# touch_rev1.net
KiCad netlist of a schematic drawn in EAGLE
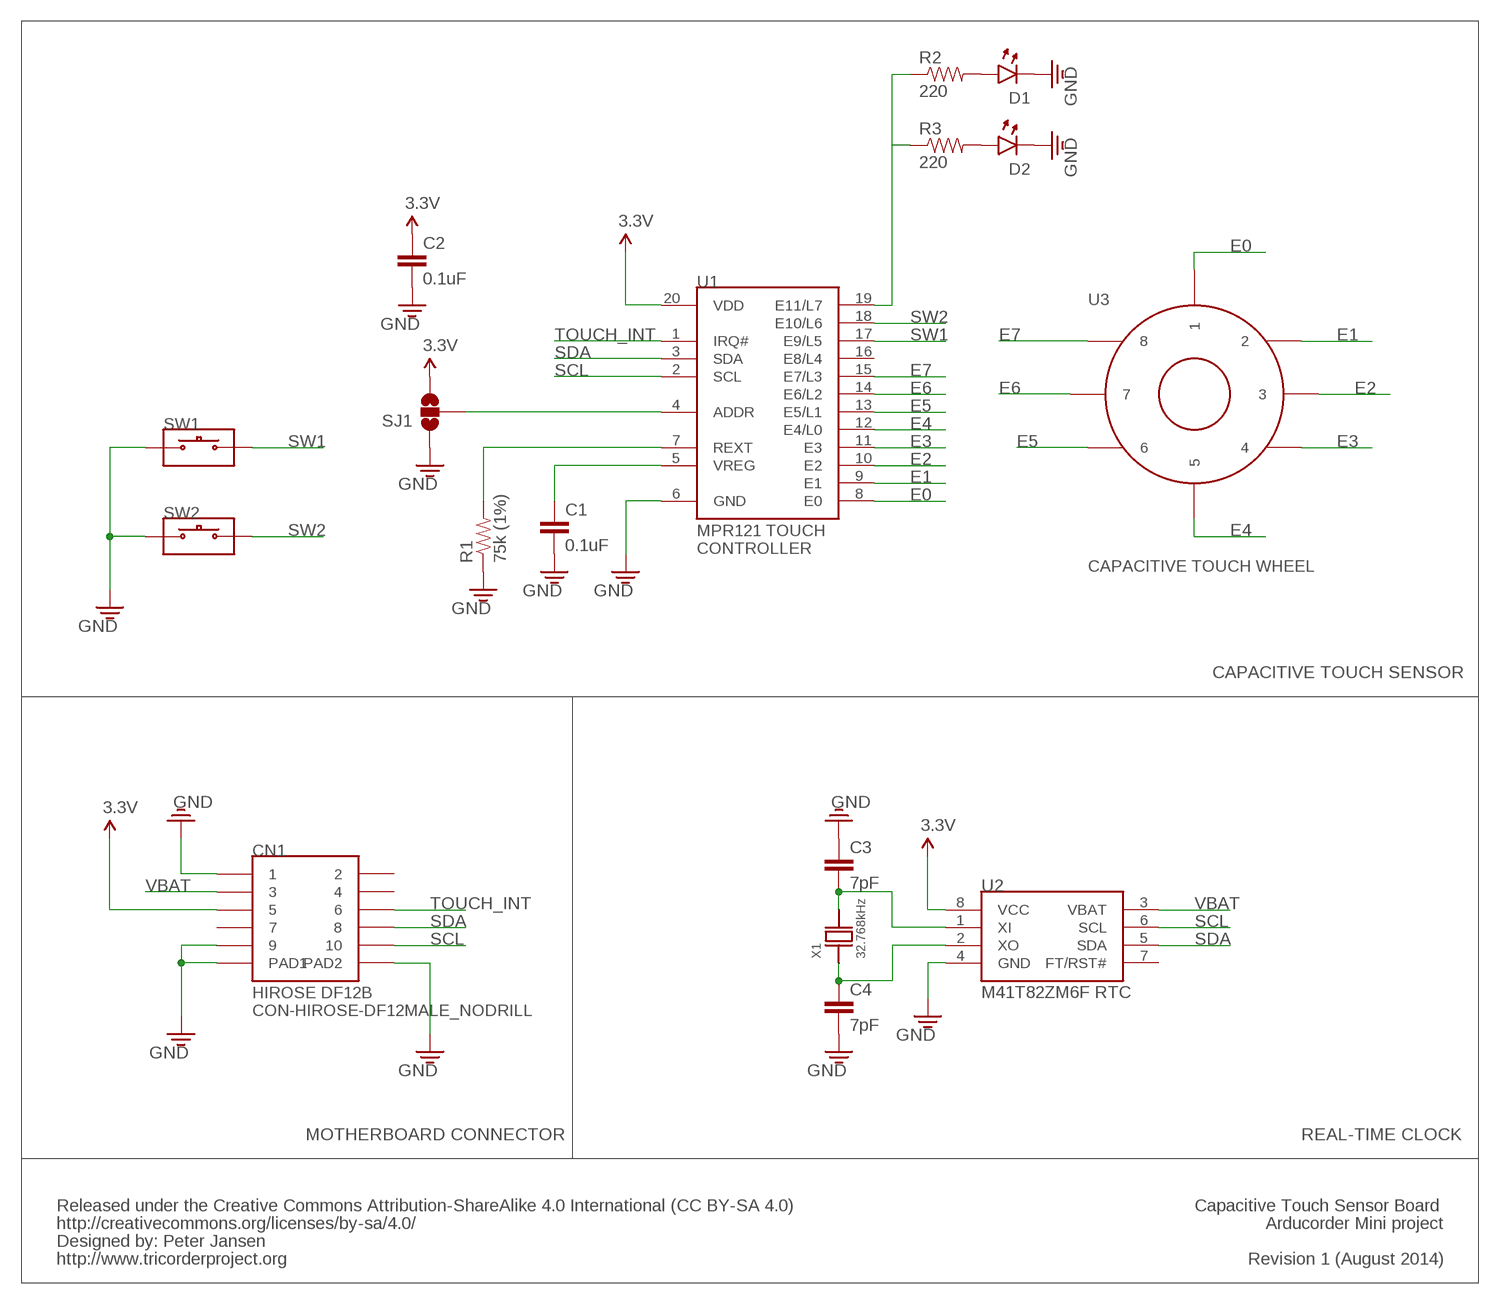
[diagram p0: schematic, sheet 1]

(export (version "E")
  (design (tool "Eeschema 10.0.6"))
  (components
    (comp (ref "C1")
      (value "0.1uF")
      (footprint "eagle-import:0603")
      (libsource (lib "eagle-import") (part "CAP0603"))
    )
    (comp (ref "C2")
      (value "0.1uF")
      (footprint "eagle-import:0603")
      (libsource (lib "eagle-import") (part "CAP0603"))
    )
    (comp (ref "C3")
      (value "7pF")
      (footprint "eagle-import:0603")
      (libsource (lib "eagle-import") (part "CAP0603"))
    )
    (comp (ref "C4")
      (value "7pF")
      (footprint "eagle-import:0603")
      (libsource (lib "eagle-import") (part "CAP0603"))
    )
    (comp (ref "CN1")
      (value "CON-HIROSE-DF12MALE_NODRILL")
      (footprint "eagle-import:DF12(3.0)-10DS-0.5V(86)")
      (libsource (lib "eagle-import") (part "CON-HIROSE-DF12MALE_NODRILL"))
    )
    (comp (ref "D1")
      (value "0605-LED")
      (footprint "eagle-import:0603-LED")
      (libsource (lib "eagle-import") (part "0605-LED"))
    )
    (comp (ref "D2")
      (value "0605-LED")
      (footprint "eagle-import:0603-LED")
      (libsource (lib "eagle-import") (part "0605-LED"))
    )
    (comp (ref "R1")
      (value "75k (1%)")
      (footprint "eagle-import:0603")
      (libsource (lib "eagle-import") (part "RESISTOR0603"))
    )
    (comp (ref "R2")
      (value "220")
      (footprint "eagle-import:0603")
      (libsource (lib "eagle-import") (part "RESISTOR0603"))
    )
    (comp (ref "R3")
      (value "220")
      (footprint "eagle-import:0603")
      (libsource (lib "eagle-import") (part "RESISTOR0603"))
    )
    (comp (ref "SJ1")
      (value "SOLDERJUMPER_2WAYPASTE1&2")
      (footprint "eagle-import:SJ_3_PASTE1&2")
      (libsource (lib "eagle-import") (part "SOLDERJUMPER_2WAYPASTE1&2"))
    )
    (comp (ref "SW1")
      (value "SWITCH")
      (footprint "eagle-import:KMT071")
      (libsource (lib "eagle-import") (part "SWITCH"))
    )
    (comp (ref "SW2")
      (value "SWITCH")
      (footprint "eagle-import:KMT071")
      (libsource (lib "eagle-import") (part "SWITCH"))
    )
    (comp (ref "U1")
      (value "MPR121-TOUCH-CONTROLLER")
      (footprint "eagle-import:QFN-3X3-20")
      (libsource (lib "eagle-import") (part "MPR121-TOUCH-CONTROLLER"))
    )
    (comp (ref "U2")
      (value "M41T82ZM6F")
      (footprint "eagle-import:8-SOIC")
      (libsource (lib "eagle-import") (part "M41T82ZM6F"))
    )
    (comp (ref "U3")
      (value "CAPACITIVE-WHEEL-8")
      (footprint "eagle-import:CAPACITIVE-WHEEL-8")
      (libsource (lib "eagle-import") (part "CAPACITIVE-WHEEL-8"))
    )
    (comp (ref "X1")
      (value "32.768kHz")
      (footprint "eagle-import:CRYSTAL-9HT10")
      (libsource (lib "eagle-import") (part "CRYSTAL"))
    )
  )
  (nets
    (net (code "1") (name "/E0") (class "Default")
      (node (ref "U1") (pin "8") (pinfunction "E0_8") (pintype "bidirectional"))
      (node (ref "U3") (pin "1") (pinfunction "1_1") (pintype "bidirectional"))
    )
    (net (code "2") (name "/E1") (class "Default")
      (node (ref "U1") (pin "9") (pinfunction "E1_9") (pintype "bidirectional"))
      (node (ref "U3") (pin "2") (pinfunction "2_2") (pintype "bidirectional"))
    )
    (net (code "3") (name "/E2") (class "Default")
      (node (ref "U1") (pin "10") (pinfunction "E2_10") (pintype "bidirectional"))
      (node (ref "U3") (pin "3") (pinfunction "3_3") (pintype "bidirectional"))
    )
    (net (code "4") (name "/E3") (class "Default")
      (node (ref "U1") (pin "11") (pinfunction "E3_11") (pintype "bidirectional"))
      (node (ref "U3") (pin "4") (pinfunction "4_4") (pintype "bidirectional"))
    )
    (net (code "5") (name "/E4") (class "Default")
      (node (ref "U1") (pin "12") (pinfunction "E4/L0_12") (pintype "bidirectional"))
      (node (ref "U3") (pin "5") (pinfunction "5_5") (pintype "bidirectional"))
    )
    (net (code "6") (name "/E5") (class "Default")
      (node (ref "U1") (pin "13") (pinfunction "E5/L1_13") (pintype "bidirectional"))
      (node (ref "U3") (pin "6") (pinfunction "6_6") (pintype "bidirectional"))
    )
    (net (code "7") (name "/E6") (class "Default")
      (node (ref "U1") (pin "14") (pinfunction "E6/L2_14") (pintype "bidirectional"))
      (node (ref "U3") (pin "7") (pinfunction "7_7") (pintype "bidirectional"))
    )
    (net (code "8") (name "/E7") (class "Default")
      (node (ref "U1") (pin "15") (pinfunction "E7/L3_15") (pintype "bidirectional"))
      (node (ref "U3") (pin "8") (pinfunction "8_8") (pintype "bidirectional"))
    )
    (net (code "9") (name "/SCL") (class "Default")
      (node (ref "CN1") (pin "10") (pinfunction "10_10") (pintype "bidirectional"))
      (node (ref "U1") (pin "2") (pinfunction "SCL_2") (pintype "bidirectional"))
      (node (ref "U2") (pin "6") (pinfunction "SCL_6") (pintype "bidirectional"))
    )
    (net (code "10") (name "/SDA") (class "Default")
      (node (ref "CN1") (pin "8") (pinfunction "8_8") (pintype "bidirectional"))
      (node (ref "U1") (pin "3") (pinfunction "SDA_3") (pintype "bidirectional"))
      (node (ref "U2") (pin "5") (pinfunction "SDA_5") (pintype "bidirectional"))
    )
    (net (code "11") (name "/SW1") (class "Default")
      (node (ref "SW1") (pin "2A") (pinfunction "2A_2A") (pintype "bidirectional"))
      (node (ref "U1") (pin "17") (pinfunction "E9/L5_17") (pintype "bidirectional"))
    )
    (net (code "12") (name "/SW2") (class "Default")
      (node (ref "SW2") (pin "2A") (pinfunction "2A_2A") (pintype "bidirectional"))
      (node (ref "U1") (pin "18") (pinfunction "E10/L6_18") (pintype "bidirectional"))
    )
    (net (code "13") (name "/TOUCH_INT") (class "Default")
      (node (ref "CN1") (pin "6") (pinfunction "6_6") (pintype "bidirectional"))
      (node (ref "U1") (pin "1") (pinfunction "IRQ#_1") (pintype "bidirectional"))
    )
    (net (code "14") (name "/VBAT") (class "Default")
      (node (ref "CN1") (pin "3") (pinfunction "3_3") (pintype "bidirectional"))
      (node (ref "U2") (pin "3") (pinfunction "VBAT_3") (pintype "bidirectional"))
    )
    (net (code "15") (name "3.3V") (class "Default")
      (node (ref "C2") (pin "1") (pinfunction "1_1") (pintype "passive"))
      (node (ref "CN1") (pin "5") (pinfunction "5_5") (pintype "bidirectional"))
      (node (ref "SJ1") (pin "3") (pinfunction "3_3") (pintype "passive"))
      (node (ref "U1") (pin "20") (pinfunction "VDD_20") (pintype "bidirectional"))
      (node (ref "U2") (pin "8") (pinfunction "VCC_8") (pintype "bidirectional"))
    )
    (net (code "16") (name "GND") (class "Default")
      (node (ref "C1") (pin "2") (pinfunction "2_2") (pintype "passive"))
      (node (ref "C2") (pin "2") (pinfunction "2_2") (pintype "passive"))
      (node (ref "C3") (pin "1") (pinfunction "1_1") (pintype "passive"))
      (node (ref "C4") (pin "2") (pinfunction "2_2") (pintype "passive"))
      (node (ref "CN1") (pin "1") (pinfunction "1_1") (pintype "bidirectional"))
      (node (ref "CN1") (pin "9") (pinfunction "9_9") (pintype "bidirectional"))
      (node (ref "CN1") (pin "PAD1") (pinfunction "PAD1_PAD1") (pintype "bidirectional"))
      (node (ref "CN1") (pin "PAD2") (pinfunction "PAD2_PAD2") (pintype "bidirectional"))
      (node (ref "D1") (pin "CATHODE") (pinfunction "CATHODE_CATHODE") (pintype "bidirectional"))
      (node (ref "D2") (pin "CATHODE") (pinfunction "CATHODE_CATHODE") (pintype "bidirectional"))
      (node (ref "R1") (pin "1") (pinfunction "1_1") (pintype "passive"))
      (node (ref "SJ1") (pin "1") (pinfunction "1_1") (pintype "passive"))
      (node (ref "SW1") (pin "1A") (pinfunction "1A_1A") (pintype "bidirectional"))
      (node (ref "SW2") (pin "1A") (pinfunction "1A_1A") (pintype "bidirectional"))
      (node (ref "U1") (pin "6") (pinfunction "GND_6") (pintype "bidirectional"))
      (node (ref "U2") (pin "4") (pinfunction "GND_4") (pintype "bidirectional"))
    )
    (net (code "17") (name "Net-(D1-PadANODE)") (class "Default")
      (node (ref "D1") (pin "ANODE") (pinfunction "ANODE_ANODE") (pintype "bidirectional"))
      (node (ref "R2") (pin "2") (pinfunction "2_2") (pintype "passive"))
    )
    (net (code "18") (name "Net-(D2-PadANODE)") (class "Default")
      (node (ref "D2") (pin "ANODE") (pinfunction "ANODE_ANODE") (pintype "bidirectional"))
      (node (ref "R3") (pin "2") (pinfunction "2_2") (pintype "passive"))
    )
    (net (code "19") (name "Net-(U1-ADDR)") (class "Default")
      (node (ref "SJ1") (pin "2") (pinfunction "2_2") (pintype "passive"))
      (node (ref "U1") (pin "4") (pinfunction "ADDR_4") (pintype "bidirectional"))
    )
    (net (code "20") (name "Net-(U1-E11{slash}L7)") (class "Default")
      (node (ref "R2") (pin "1") (pinfunction "1_1") (pintype "passive"))
      (node (ref "R3") (pin "1") (pinfunction "1_1") (pintype "passive"))
      (node (ref "U1") (pin "19") (pinfunction "E11/L7_19") (pintype "bidirectional"))
    )
    (net (code "21") (name "Net-(U1-REXT)") (class "Default")
      (node (ref "R1") (pin "2") (pinfunction "2_2") (pintype "passive"))
      (node (ref "U1") (pin "7") (pinfunction "REXT_7") (pintype "bidirectional"))
    )
    (net (code "22") (name "Net-(U1-VREG)") (class "Default")
      (node (ref "C1") (pin "1") (pinfunction "1_1") (pintype "passive"))
      (node (ref "U1") (pin "5") (pinfunction "VREG_5") (pintype "bidirectional"))
    )
    (net (code "23") (name "Net-(U2-XI)") (class "Default")
      (node (ref "C3") (pin "2") (pinfunction "2_2") (pintype "passive"))
      (node (ref "U2") (pin "1") (pinfunction "XI_1") (pintype "bidirectional"))
      (node (ref "X1") (pin "2") (pinfunction "2_2") (pintype "bidirectional"))
    )
    (net (code "24") (name "Net-(U2-XO)") (class "Default")
      (node (ref "C4") (pin "1") (pinfunction "1_1") (pintype "passive"))
      (node (ref "U2") (pin "2") (pinfunction "XO_2") (pintype "bidirectional"))
      (node (ref "X1") (pin "1") (pinfunction "1_1") (pintype "bidirectional"))
    )
    (net (code "25") (name "unconnected-(CN1-Pad2)") (class "Default")
      (node (ref "CN1") (pin "2") (pinfunction "2_2") (pintype "bidirectional"))
    )
    (net (code "26") (name "unconnected-(CN1-Pad4)") (class "Default")
      (node (ref "CN1") (pin "4") (pinfunction "4_4") (pintype "bidirectional"))
    )
    (net (code "27") (name "unconnected-(CN1-Pad7)") (class "Default")
      (node (ref "CN1") (pin "7") (pinfunction "7_7") (pintype "bidirectional"))
    )
    (net (code "28") (name "unconnected-(U1-E8{slash}L4-Pad16)") (class "Default")
      (node (ref "U1") (pin "16") (pinfunction "E8/L4_16") (pintype "bidirectional"))
    )
    (net (code "29") (name "unconnected-(U2-FT{slash}RST#-Pad7)") (class "Default")
      (node (ref "U2") (pin "7") (pinfunction "FT/RST#_7") (pintype "bidirectional"))
    )
  )
)
